# ESP32.net
KiCad netlist of a schematic drawn in Altium Designer
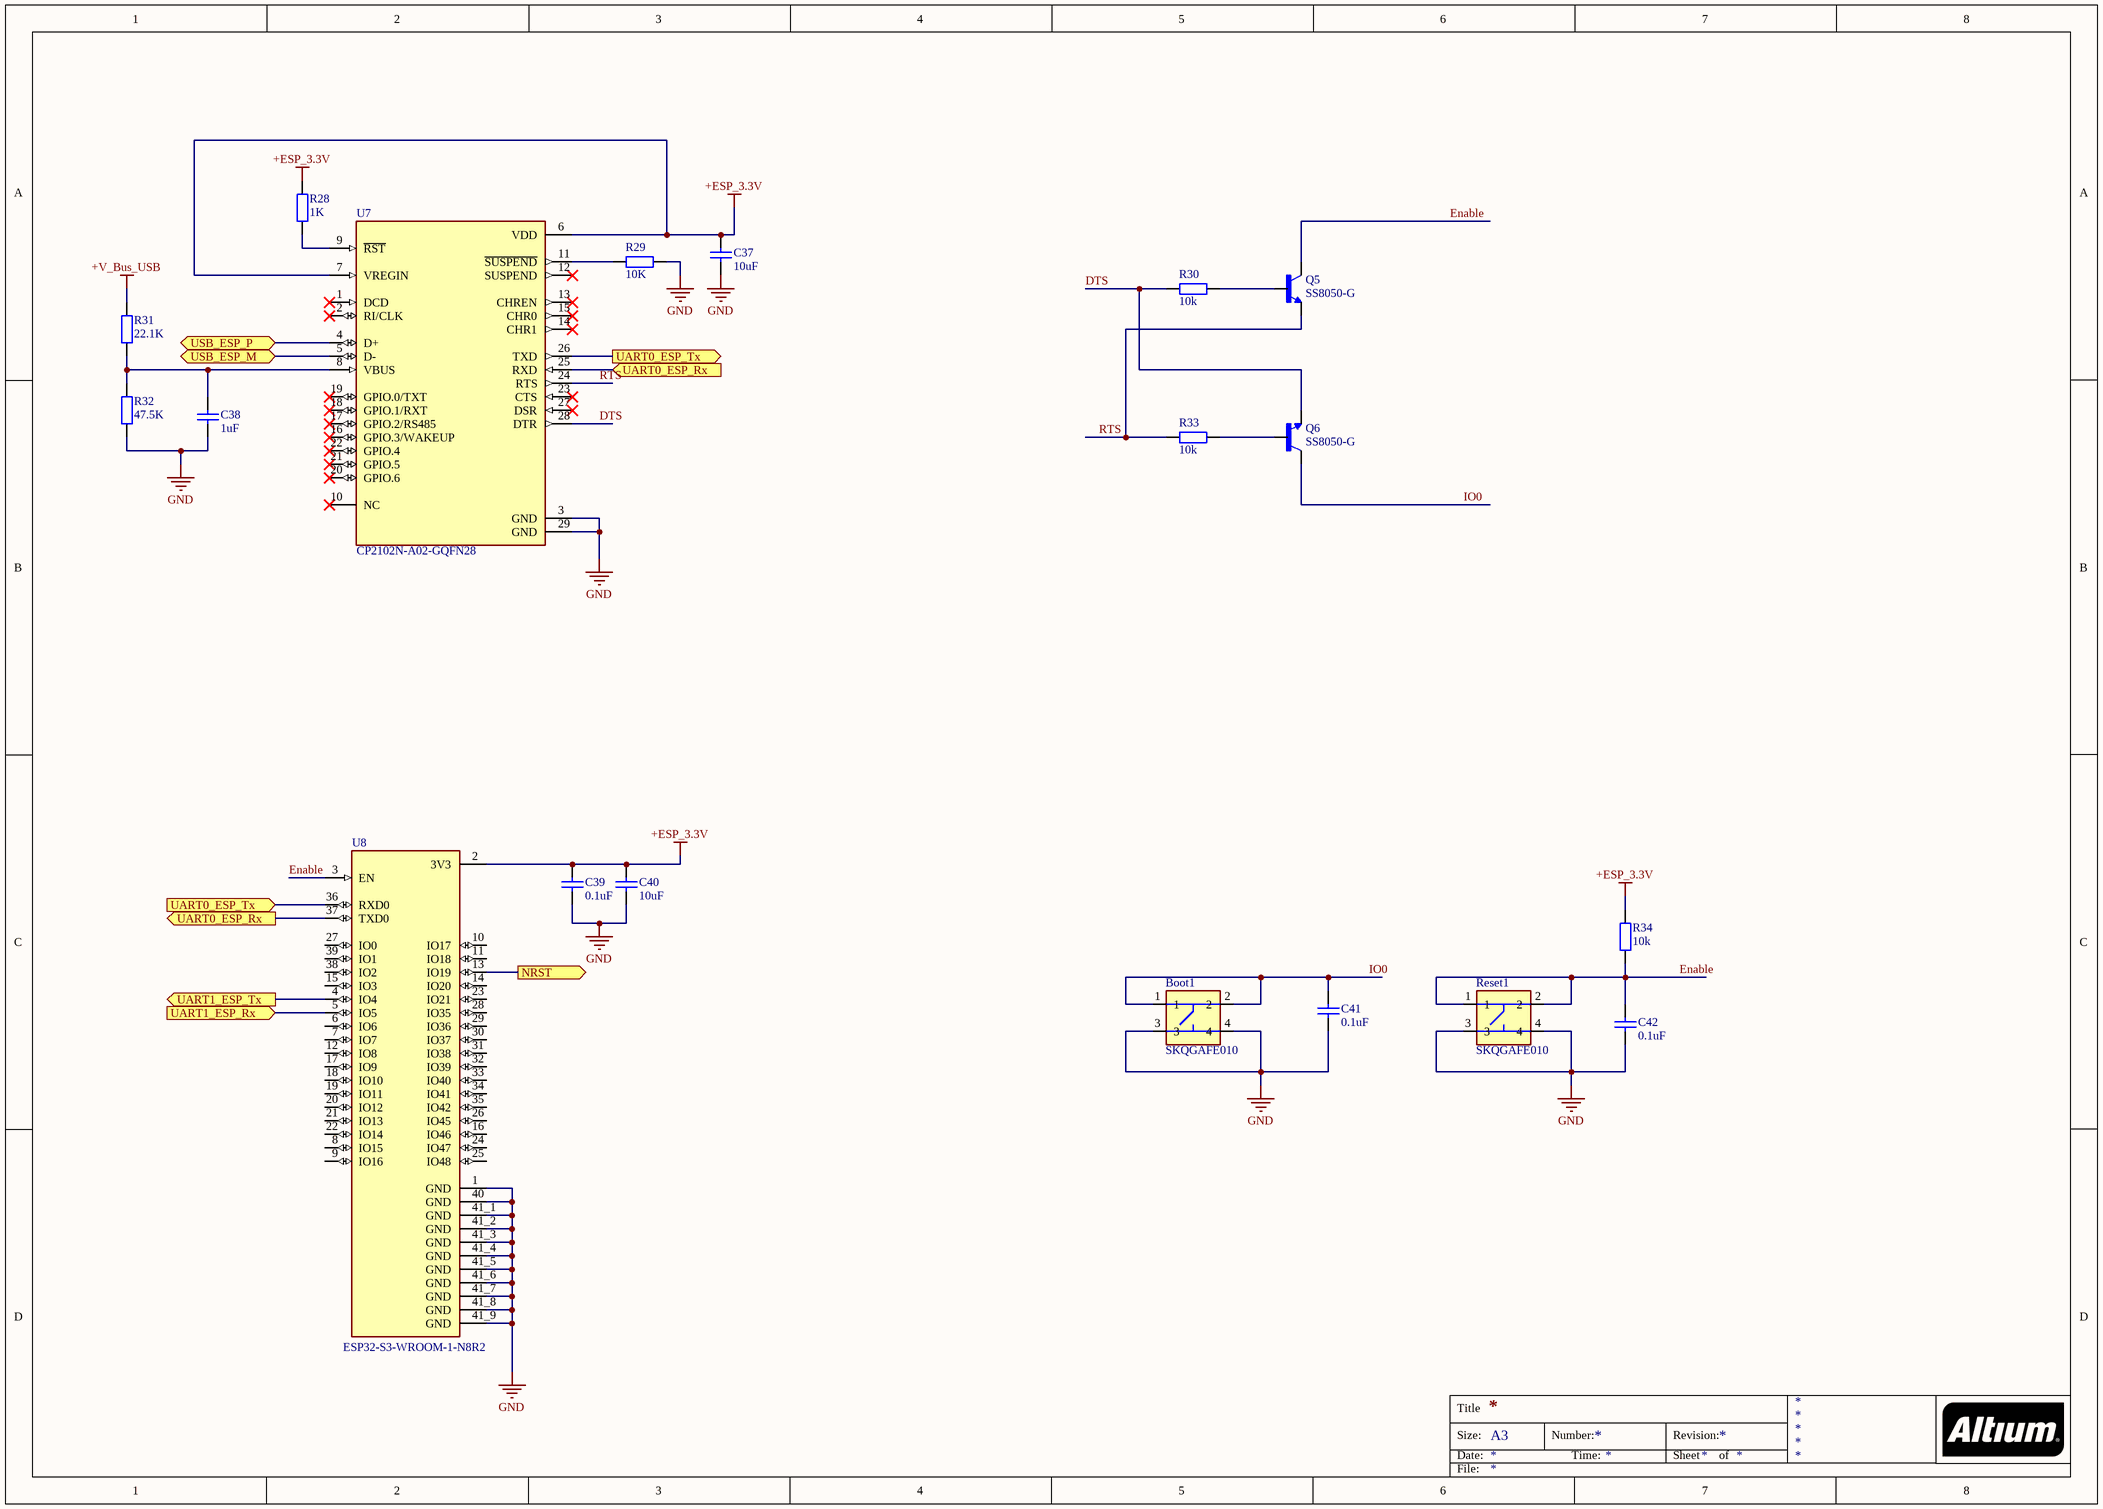
[diagram p0: ESP32.SchDoc]

(export (version "E")
  (design (tool "Eeschema 10.0.6"))
  (components
    (comp (ref "Boot1")
      (value "SKQGAFE010")
      (footprint "SKQGAFE010:SW_SKQGAFE010")
      (description "Switch Tactile N.O. SPST Button Gull Wing 0.05A 12VDC 0.98N SMD T/R")
      (fields (field (name "MF") "{'manufacturer': u'ALPS'}"))
      (libsource (lib "*") (part "SKQGAFE010"))
    )
    (comp (ref "C37")
      (value "10uF")
      (footprint "tu 0805")
      (description "Dán")
      (libsource (lib "Altium_Lib_by_KhueNguyenCreator") (part "Tu 0805 10pF 50V 10%"))
    )
    (comp (ref "C38")
      (value "1uF")
      (footprint "tu 0805")
      (description "Dán")
      (libsource (lib "Altium_Lib_by_KhueNguyenCreator") (part "Tu 0805 10pF 50V 10%"))
    )
    (comp (ref "C39")
      (value "0.1uF")
      (footprint "tu 0805")
      (description "Dán")
      (libsource (lib "Altium_Lib_by_KhueNguyenCreator") (part "Tu 0805 10pF 50V 10%"))
    )
    (comp (ref "C40")
      (value "10uF")
      (footprint "tu 0805")
      (description "Dán")
      (libsource (lib "Altium_Lib_by_KhueNguyenCreator") (part "Tu 0805 10pF 50V 10%"))
    )
    (comp (ref "C41")
      (value "0.1uF")
      (footprint "tu 0805")
      (description "Dán")
      (libsource (lib "Altium_Lib_by_KhueNguyenCreator") (part "Tu 0805 10pF 50V 10%"))
    )
    (comp (ref "C42")
      (value "0.1uF")
      (footprint "tu 0805")
      (description "Dán")
      (libsource (lib "Altium_Lib_by_KhueNguyenCreator") (part "Tu 0805 10pF 50V 10%"))
    )
    (comp (ref "Q5")
      (value "SS8050-G")
      (footprint "TRANS_SS8050-G")
      (description "Bipolar (BJT) Transistor NPN 25 V 1.5 A 100MHz 300 mW Surface Mount SOT-23-3")
      (fields (field (name "MF") "{'manufacturer': u'Comchip Technology'}"))
      (libsource (lib "SnapEDA_Library") (part "SS8050-G"))
    )
    (comp (ref "Q6")
      (value "SS8050-G")
      (footprint "TRANS_SS8050-G")
      (description "Bipolar (BJT) Transistor NPN 25 V 1.5 A 100MHz 300 mW Surface Mount SOT-23-3")
      (fields (field (name "MF") "{'manufacturer': u'Comchip Technology'}"))
      (libsource (lib "") (part "SS8050-G_1"))
    )
    (comp (ref "R28")
      (value "1K")
      (footprint "tro smd 0805")
      (description "Dán")
      (libsource (lib "Altium_Lib_by_KhueNguyenCreator") (part "Tro 0805 1% 1k"))
    )
    (comp (ref "R29")
      (value "10K")
      (footprint "tro smd 0805")
      (description "Dán")
      (libsource (lib "Altium_Lib_by_KhueNguyenCreator") (part "Tro 0805 1% 1k"))
    )
    (comp (ref "R30")
      (value "10k")
      (footprint "tro smd 0805")
      (description "Dán")
      (libsource (lib "Altium_Lib_by_KhueNguyenCreator") (part "Tro 0805 1% 1k"))
    )
    (comp (ref "R31")
      (value "22.1K")
      (footprint "tro smd 0805")
      (description "Dán")
      (libsource (lib "Altium_Lib_by_KhueNguyenCreator") (part "Tro 0805 1% 1k"))
    )
    (comp (ref "R32")
      (value "47.5K")
      (footprint "tro smd 0805")
      (description "Dán")
      (libsource (lib "Altium_Lib_by_KhueNguyenCreator") (part "Tro 0805 1% 1k"))
    )
    (comp (ref "R33")
      (value "10k")
      (footprint "tro smd 0805")
      (description "Dán")
      (libsource (lib "Altium_Lib_by_KhueNguyenCreator") (part "Tro 0805 1% 1k"))
    )
    (comp (ref "R34")
      (value "10k")
      (footprint "tro smd 0805")
      (description "Dán")
      (libsource (lib "Altium_Lib_by_KhueNguyenCreator") (part "Tro 0805 1% 1k"))
    )
    (comp (ref "Reset1")
      (value "SKQGAFE010")
      (footprint "SKQGAFE010:SW_SKQGAFE010")
      (description "Switch Tactile N.O. SPST Button Gull Wing 0.05A 12VDC 0.98N SMD T/R")
      (fields (field (name "MF") "{'manufacturer': u'ALPS'}"))
      (libsource (lib "*") (part "SKQGAFE010"))
    )
    (comp (ref "U7")
      (value "CP2102N-A02-GQFN28")
      (footprint "QFN50P500X500X80-29N")
      (fields (field (name "MF") "{'manufacturer': u'Silicon Labs'}"))
      (libsource (lib "SnapEDA_Library") (part "CP2102N-A02-GQFN28"))
    )
    (comp (ref "U8")
      (value "ESP32-S3-WROOM-1-N8R2")
      (footprint "ESP32-S3-WROOM-1-N8R2:XCVR_ESP32-S3-WROOM-1-N8R2")
      (fields (field (name "MF") "{'manufacturer': u'Espressif Systems'}"))
      (libsource (lib "*") (part "ESP32-S3-WROOM-1-N8R2"))
    )
  )
  (nets
    (net (code "1") (name "+ESP_3.3V") (class "Default")
      (node (ref "C37") (pin "1") (pinfunction "1_1") (pintype "passive"))
      (node (ref "C39") (pin "2") (pinfunction "2_2") (pintype "passive"))
      (node (ref "C40") (pin "1") (pinfunction "1_1") (pintype "passive"))
      (node (ref "R28") (pin "2") (pinfunction "2_2") (pintype "passive"))
      (node (ref "R34") (pin "2") (pinfunction "2_2") (pintype "passive"))
      (node (ref "U7") (pin "6") (pinfunction "VDD_6") (pintype "power_in"))
      (node (ref "U7") (pin "7") (pinfunction "VREGIN_7") (pintype "input"))
      (node (ref "U8") (pin "2") (pinfunction "3V3_2") (pintype "power_in"))
    )
    (net (code "2") (name "+V_Bus_USB") (class "Default")
      (node (ref "R31") (pin "1") (pinfunction "1_1") (pintype "passive"))
    )
    (net (code "3") (name "/DTS") (class "Default")
      (node (ref "Q6") (pin "2") (pinfunction "E_2") (pintype "passive"))
      (node (ref "R30") (pin "1") (pinfunction "1_1") (pintype "passive"))
      (node (ref "U7") (pin "28") (pinfunction "DTR_28") (pintype "output"))
    )
    (net (code "4") (name "/Enable") (class "Default")
      (node (ref "C42") (pin "2") (pinfunction "2_2") (pintype "passive"))
      (node (ref "Q5") (pin "3") (pinfunction "C_3") (pintype "passive"))
      (node (ref "R34") (pin "1") (pinfunction "1_1") (pintype "passive"))
      (node (ref "Reset1") (pin "1") (pinfunction "1_1") (pintype "passive"))
      (node (ref "Reset1") (pin "2") (pinfunction "2_2") (pintype "passive"))
      (node (ref "U8") (pin "3") (pinfunction "EN_3") (pintype "input"))
    )
    (net (code "5") (name "/IO0") (class "Default")
      (node (ref "Boot1") (pin "1") (pinfunction "1_1") (pintype "passive"))
      (node (ref "Boot1") (pin "2") (pinfunction "2_2") (pintype "passive"))
      (node (ref "C41") (pin "2") (pinfunction "2_2") (pintype "passive"))
      (node (ref "Q6") (pin "3") (pinfunction "C_3") (pintype "passive"))
    )
    (net (code "6") (name "/NRST") (class "Default")
      (node (ref "U8") (pin "13") (pinfunction "IO19_13") (pintype "bidirectional"))
    )
    (net (code "7") (name "/RTS") (class "Default")
      (node (ref "Q5") (pin "2") (pinfunction "E_2") (pintype "passive"))
      (node (ref "R33") (pin "1") (pinfunction "1_1") (pintype "passive"))
      (node (ref "U7") (pin "24") (pinfunction "RTS_24") (pintype "output"))
    )
    (net (code "8") (name "/UART0_ESP_Rx") (class "Default")
      (node (ref "U7") (pin "25") (pinfunction "RXD_25") (pintype "input"))
      (node (ref "U8") (pin "37") (pinfunction "TXD0_37") (pintype "bidirectional"))
    )
    (net (code "9") (name "/UART0_ESP_Tx") (class "Default")
      (node (ref "U7") (pin "26") (pinfunction "TXD_26") (pintype "output"))
      (node (ref "U8") (pin "36") (pinfunction "RXD0_36") (pintype "bidirectional"))
    )
    (net (code "10") (name "/UART1_ESP_Rx") (class "Default")
      (node (ref "U8") (pin "5") (pinfunction "IO5_5") (pintype "bidirectional"))
    )
    (net (code "11") (name "/UART1_ESP_Tx") (class "Default")
      (node (ref "U8") (pin "4") (pinfunction "IO4_4") (pintype "bidirectional"))
    )
    (net (code "12") (name "/USB_ESP_M") (class "Default")
      (node (ref "U7") (pin "5") (pinfunction "D-_5") (pintype "bidirectional"))
    )
    (net (code "13") (name "/USB_ESP_P") (class "Default")
      (node (ref "U7") (pin "4") (pinfunction "D+_4") (pintype "bidirectional"))
    )
    (net (code "14") (name "GND") (class "Default")
      (node (ref "Boot1") (pin "3") (pinfunction "3_3") (pintype "passive"))
      (node (ref "Boot1") (pin "4") (pinfunction "4_4") (pintype "passive"))
      (node (ref "C37") (pin "2") (pinfunction "2_2") (pintype "passive"))
      (node (ref "C38") (pin "2") (pinfunction "2_2") (pintype "passive"))
      (node (ref "C39") (pin "1") (pinfunction "1_1") (pintype "passive"))
      (node (ref "C40") (pin "2") (pinfunction "2_2") (pintype "passive"))
      (node (ref "C41") (pin "1") (pinfunction "1_1") (pintype "passive"))
      (node (ref "C42") (pin "1") (pinfunction "1_1") (pintype "passive"))
      (node (ref "R29") (pin "1") (pinfunction "1_1") (pintype "passive"))
      (node (ref "R32") (pin "1") (pinfunction "1_1") (pintype "passive"))
      (node (ref "Reset1") (pin "3") (pinfunction "3_3") (pintype "passive"))
      (node (ref "Reset1") (pin "4") (pinfunction "4_4") (pintype "passive"))
      (node (ref "U7") (pin "29") (pinfunction "GND_29") (pintype "power_in"))
      (node (ref "U7") (pin "3") (pinfunction "GND_3") (pintype "power_in"))
      (node (ref "U8") (pin "1") (pinfunction "GND_1") (pintype "power_in"))
      (node (ref "U8") (pin "40") (pinfunction "GND_40") (pintype "power_in"))
      (node (ref "U8") (pin "41_1") (pinfunction "GND_41_1") (pintype "power_in"))
      (node (ref "U8") (pin "41_2") (pinfunction "GND_41_2") (pintype "power_in"))
      (node (ref "U8") (pin "41_3") (pinfunction "GND_41_3") (pintype "power_in"))
      (node (ref "U8") (pin "41_4") (pinfunction "GND_41_4") (pintype "power_in"))
      (node (ref "U8") (pin "41_5") (pinfunction "GND_41_5") (pintype "power_in"))
      (node (ref "U8") (pin "41_6") (pinfunction "GND_41_6") (pintype "power_in"))
      (node (ref "U8") (pin "41_7") (pinfunction "GND_41_7") (pintype "power_in"))
      (node (ref "U8") (pin "41_8") (pinfunction "GND_41_8") (pintype "power_in"))
      (node (ref "U8") (pin "41_9") (pinfunction "GND_41_9") (pintype "power_in"))
    )
    (net (code "15") (name "Net-(Q5-B)") (class "Default")
      (node (ref "Q5") (pin "1") (pinfunction "B_1") (pintype "passive"))
      (node (ref "R30") (pin "2") (pinfunction "2_2") (pintype "passive"))
    )
    (net (code "16") (name "Net-(Q6-B)") (class "Default")
      (node (ref "Q6") (pin "1") (pinfunction "B_1") (pintype "passive"))
      (node (ref "R33") (pin "2") (pinfunction "2_2") (pintype "passive"))
    )
    (net (code "17") (name "Net-(U7-VBUS)") (class "Default")
      (node (ref "C38") (pin "1") (pinfunction "1_1") (pintype "passive"))
      (node (ref "R31") (pin "2") (pinfunction "2_2") (pintype "passive"))
      (node (ref "R32") (pin "2") (pinfunction "2_2") (pintype "passive"))
      (node (ref "U7") (pin "8") (pinfunction "VBUS_8") (pintype "input"))
    )
    (net (code "18") (name "Net-(U7-~{RST})") (class "Default")
      (node (ref "R28") (pin "1") (pinfunction "1_1") (pintype "passive"))
      (node (ref "U7") (pin "9") (pinfunction "~{RST}_9") (pintype "input"))
    )
    (net (code "19") (name "Net-(U7-~{SUSPEND})") (class "Default")
      (node (ref "R29") (pin "2") (pinfunction "2_2") (pintype "passive"))
      (node (ref "U7") (pin "11") (pinfunction "~{SUSPEND}_11") (pintype "output"))
    )
    (net (code "20") (name "unconnected-(U7-CHR0-Pad15)") (class "Default")
      (node (ref "U7") (pin "15") (pinfunction "CHR0_15") (pintype "output+no_connect"))
    )
    (net (code "21") (name "unconnected-(U7-CHR1-Pad14)") (class "Default")
      (node (ref "U7") (pin "14") (pinfunction "CHR1_14") (pintype "output+no_connect"))
    )
    (net (code "22") (name "unconnected-(U7-CHREN-Pad13)") (class "Default")
      (node (ref "U7") (pin "13") (pinfunction "CHREN_13") (pintype "output+no_connect"))
    )
    (net (code "23") (name "unconnected-(U7-CTS-Pad23)") (class "Default")
      (node (ref "U7") (pin "23") (pinfunction "CTS_23") (pintype "input+no_connect"))
    )
    (net (code "24") (name "unconnected-(U7-DCD-Pad1)") (class "Default")
      (node (ref "U7") (pin "1") (pinfunction "DCD_1") (pintype "input+no_connect"))
    )
    (net (code "25") (name "unconnected-(U7-DSR-Pad27)") (class "Default")
      (node (ref "U7") (pin "27") (pinfunction "DSR_27") (pintype "input+no_connect"))
    )
    (net (code "26") (name "unconnected-(U7-GPIO.0{slash}TXT-Pad19)") (class "Default")
      (node (ref "U7") (pin "19") (pinfunction "GPIO.0/TXT_19") (pintype "bidirectional+no_connect"))
    )
    (net (code "27") (name "unconnected-(U7-GPIO.1{slash}RXT-Pad18)") (class "Default")
      (node (ref "U7") (pin "18") (pinfunction "GPIO.1/RXT_18") (pintype "bidirectional+no_connect"))
    )
    (net (code "28") (name "unconnected-(U7-GPIO.2{slash}RS485-Pad17)") (class "Default")
      (node (ref "U7") (pin "17") (pinfunction "GPIO.2/RS485_17") (pintype "bidirectional+no_connect"))
    )
    (net (code "29") (name "unconnected-(U7-GPIO.3{slash}WAKEUP-Pad16)") (class "Default")
      (node (ref "U7") (pin "16") (pinfunction "GPIO.3/WAKEUP_16") (pintype "bidirectional+no_connect"))
    )
    (net (code "30") (name "unconnected-(U7-GPIO.4-Pad22)") (class "Default")
      (node (ref "U7") (pin "22") (pinfunction "GPIO.4_22") (pintype "bidirectional+no_connect"))
    )
    (net (code "31") (name "unconnected-(U7-GPIO.5-Pad21)") (class "Default")
      (node (ref "U7") (pin "21") (pinfunction "GPIO.5_21") (pintype "bidirectional+no_connect"))
    )
    (net (code "32") (name "unconnected-(U7-GPIO.6-Pad20)") (class "Default")
      (node (ref "U7") (pin "20") (pinfunction "GPIO.6_20") (pintype "bidirectional+no_connect"))
    )
    (net (code "33") (name "unconnected-(U7-NC-Pad10)") (class "Default")
      (node (ref "U7") (pin "10") (pinfunction "NC_10") (pintype "passive+no_connect"))
    )
    (net (code "34") (name "unconnected-(U7-RI{slash}CLK-Pad2)") (class "Default")
      (node (ref "U7") (pin "2") (pinfunction "RI/CLK_2") (pintype "bidirectional+no_connect"))
    )
    (net (code "35") (name "unconnected-(U7-SUSPEND-Pad12)") (class "Default")
      (node (ref "U7") (pin "12") (pinfunction "SUSPEND_12") (pintype "output+no_connect"))
    )
    (net (code "36") (name "unconnected-(U8-IO0-Pad27)") (class "Default")
      (node (ref "U8") (pin "27") (pinfunction "IO0_27") (pintype "bidirectional"))
    )
    (net (code "37") (name "unconnected-(U8-IO1-Pad39)") (class "Default")
      (node (ref "U8") (pin "39") (pinfunction "IO1_39") (pintype "bidirectional"))
    )
    (net (code "38") (name "unconnected-(U8-IO2-Pad38)") (class "Default")
      (node (ref "U8") (pin "38") (pinfunction "IO2_38") (pintype "bidirectional"))
    )
    (net (code "39") (name "unconnected-(U8-IO3-Pad15)") (class "Default")
      (node (ref "U8") (pin "15") (pinfunction "IO3_15") (pintype "bidirectional"))
    )
    (net (code "40") (name "unconnected-(U8-IO6-Pad6)") (class "Default")
      (node (ref "U8") (pin "6") (pinfunction "IO6_6") (pintype "bidirectional"))
    )
    (net (code "41") (name "unconnected-(U8-IO7-Pad7)") (class "Default")
      (node (ref "U8") (pin "7") (pinfunction "IO7_7") (pintype "bidirectional"))
    )
    (net (code "42") (name "unconnected-(U8-IO8-Pad12)") (class "Default")
      (node (ref "U8") (pin "12") (pinfunction "IO8_12") (pintype "bidirectional"))
    )
    (net (code "43") (name "unconnected-(U8-IO9-Pad17)") (class "Default")
      (node (ref "U8") (pin "17") (pinfunction "IO9_17") (pintype "bidirectional"))
    )
    (net (code "44") (name "unconnected-(U8-IO10-Pad18)") (class "Default")
      (node (ref "U8") (pin "18") (pinfunction "IO10_18") (pintype "bidirectional"))
    )
    (net (code "45") (name "unconnected-(U8-IO11-Pad19)") (class "Default")
      (node (ref "U8") (pin "19") (pinfunction "IO11_19") (pintype "bidirectional"))
    )
    (net (code "46") (name "unconnected-(U8-IO12-Pad20)") (class "Default")
      (node (ref "U8") (pin "20") (pinfunction "IO12_20") (pintype "bidirectional"))
    )
    (net (code "47") (name "unconnected-(U8-IO13-Pad21)") (class "Default")
      (node (ref "U8") (pin "21") (pinfunction "IO13_21") (pintype "bidirectional"))
    )
    (net (code "48") (name "unconnected-(U8-IO14-Pad22)") (class "Default")
      (node (ref "U8") (pin "22") (pinfunction "IO14_22") (pintype "bidirectional"))
    )
    (net (code "49") (name "unconnected-(U8-IO15-Pad8)") (class "Default")
      (node (ref "U8") (pin "8") (pinfunction "IO15_8") (pintype "bidirectional"))
    )
    (net (code "50") (name "unconnected-(U8-IO16-Pad9)") (class "Default")
      (node (ref "U8") (pin "9") (pinfunction "IO16_9") (pintype "bidirectional"))
    )
    (net (code "51") (name "unconnected-(U8-IO17-Pad10)") (class "Default")
      (node (ref "U8") (pin "10") (pinfunction "IO17_10") (pintype "bidirectional"))
    )
    (net (code "52") (name "unconnected-(U8-IO18-Pad11)") (class "Default")
      (node (ref "U8") (pin "11") (pinfunction "IO18_11") (pintype "bidirectional"))
    )
    (net (code "53") (name "unconnected-(U8-IO20-Pad14)") (class "Default")
      (node (ref "U8") (pin "14") (pinfunction "IO20_14") (pintype "bidirectional"))
    )
    (net (code "54") (name "unconnected-(U8-IO21-Pad23)") (class "Default")
      (node (ref "U8") (pin "23") (pinfunction "IO21_23") (pintype "bidirectional"))
    )
    (net (code "55") (name "unconnected-(U8-IO35-Pad28)") (class "Default")
      (node (ref "U8") (pin "28") (pinfunction "IO35_28") (pintype "bidirectional"))
    )
    (net (code "56") (name "unconnected-(U8-IO36-Pad29)") (class "Default")
      (node (ref "U8") (pin "29") (pinfunction "IO36_29") (pintype "bidirectional"))
    )
    (net (code "57") (name "unconnected-(U8-IO37-Pad30)") (class "Default")
      (node (ref "U8") (pin "30") (pinfunction "IO37_30") (pintype "bidirectional"))
    )
    (net (code "58") (name "unconnected-(U8-IO38-Pad31)") (class "Default")
      (node (ref "U8") (pin "31") (pinfunction "IO38_31") (pintype "bidirectional"))
    )
    (net (code "59") (name "unconnected-(U8-IO39-Pad32)") (class "Default")
      (node (ref "U8") (pin "32") (pinfunction "IO39_32") (pintype "bidirectional"))
    )
    (net (code "60") (name "unconnected-(U8-IO40-Pad33)") (class "Default")
      (node (ref "U8") (pin "33") (pinfunction "IO40_33") (pintype "bidirectional"))
    )
    (net (code "61") (name "unconnected-(U8-IO41-Pad34)") (class "Default")
      (node (ref "U8") (pin "34") (pinfunction "IO41_34") (pintype "bidirectional"))
    )
    (net (code "62") (name "unconnected-(U8-IO42-Pad35)") (class "Default")
      (node (ref "U8") (pin "35") (pinfunction "IO42_35") (pintype "bidirectional"))
    )
    (net (code "63") (name "unconnected-(U8-IO45-Pad26)") (class "Default")
      (node (ref "U8") (pin "26") (pinfunction "IO45_26") (pintype "bidirectional"))
    )
    (net (code "64") (name "unconnected-(U8-IO46-Pad16)") (class "Default")
      (node (ref "U8") (pin "16") (pinfunction "IO46_16") (pintype "bidirectional"))
    )
    (net (code "65") (name "unconnected-(U8-IO47-Pad24)") (class "Default")
      (node (ref "U8") (pin "24") (pinfunction "IO47_24") (pintype "bidirectional"))
    )
    (net (code "66") (name "unconnected-(U8-IO48-Pad25)") (class "Default")
      (node (ref "U8") (pin "25") (pinfunction "IO48_25") (pintype "bidirectional"))
    )
  )
)
